# Connectors.net
KiCad netlist of a schematic drawn in Altium Designer
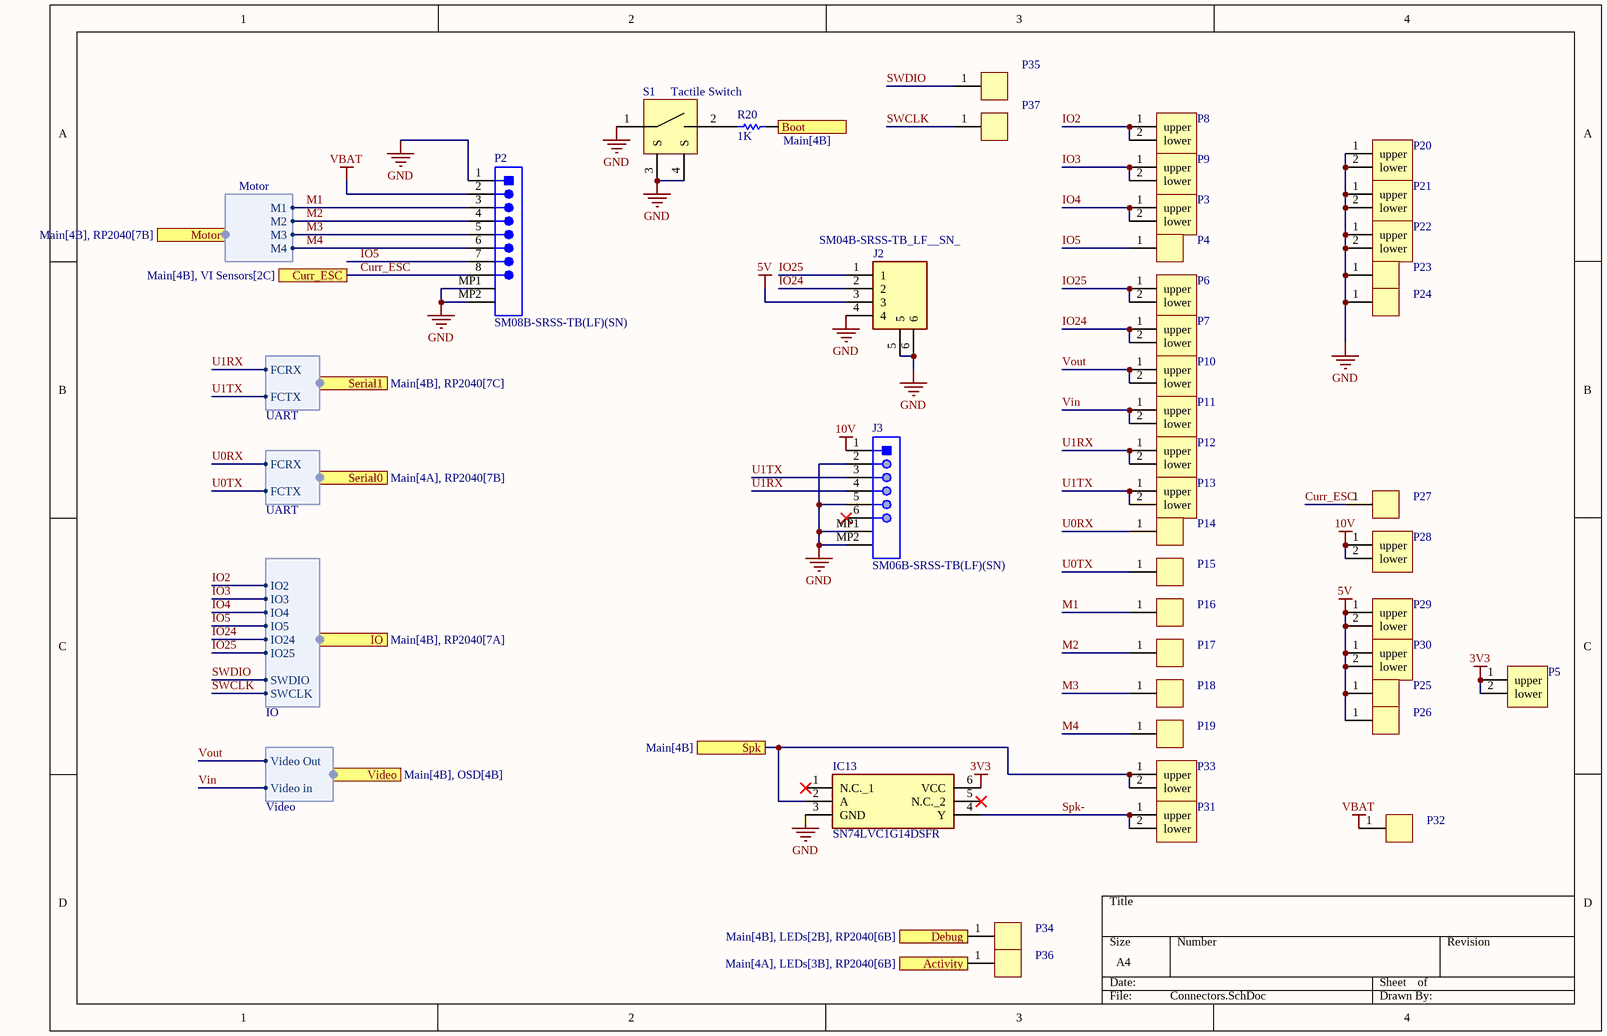
[diagram p0: Connectors.SchDoc]

(export (version "E")
  (design (tool "Eeschema 10.0.6"))
  (components
    (comp (ref "IC13")
      (value "SN74LVC1G14DSFR")
      (footprint "Custom Components:SON35P100X100X40-6N")
      (description "Integrated Circuit")
      (fields (field (name "MOUSER PART NUMBER") "595-SN74LVC1G14DSFR"))
      (libsource (lib "*") (part "SN74LVC1G14DSFR"))
    )
    (comp (ref "J2")
      (value "SM04B-SRSS-TB_LF__SN_")
      (footprint "SM04B-SRSS-TB(LFSN)")
      (description "Connector")
      (fields (field (name "MANUFACTURER_PART_NUMBER") "SM04B-SRSS-TB(LF)(SN)"))
      (libsource (lib "Custom Components") (part "SM04B-SRSS-TB_LF__SN_"))
    )
    (comp (ref "J3")
      (value "SM06B-SRSS-TB(LF)(SN)")
      (footprint "JST-SM06B-SRSS-TB_V")
      (description "Male Header, Pitch 1 mm, 1 x 6 Position, Height 2.95 mm, -25 to 85 degC, RoHS, Tape and Reel")
      (fields (field (name "MANUFACTURER") "JST"))
      (libsource (lib "Altium Content Vault") (part "CN-1P-2M-R6"))
    )
    (comp (ref "P2")
      (value "SM08B-SRSS-TB(LF)(SN)")
      (footprint "JST-SM08B-SRSS-TB_V")
      (description "Male Header, Pitch 1 mm, 1 x 8 Position, Height 2.95 mm, -25 to 85 degC, RoHS, Tape and Reel")
      (fields (field (name "MANUFACTURER") "JST"))
      (libsource (lib "Altium Content Vault") (part "CN-1P-2M-R8"))
    )
    (comp (ref "P3")
      (value "solder pad rounded double sided")
      (footprint "solder pad double sided rounded - duplicate")
      (libsource (lib "Custom Components") (part "solder pad rounded double sided"))
    )
    (comp (ref "P4")
      (value "solder pad rounded single sided")
      (footprint "solder pad single sided rounded")
      (libsource (lib "Custom Components") (part "solder pad rounded single sided"))
    )
    (comp (ref "P5")
      (value "solder pad chamfered double sided")
      (footprint "solder pad double sided chamfered")
      (libsource (lib "Custom Components") (part "solder pad chamfered double sided"))
    )
    (comp (ref "P6")
      (value "solder pad rounded double sided")
      (footprint "solder pad double sided rounded - duplicate")
      (libsource (lib "Custom Components") (part "solder pad rounded double sided"))
    )
    (comp (ref "P7")
      (value "solder pad rounded double sided")
      (footprint "solder pad double sided rounded - duplicate")
      (libsource (lib "Custom Components") (part "solder pad rounded double sided"))
    )
    (comp (ref "P8")
      (value "solder pad rounded double sided")
      (footprint "solder pad double sided rounded - duplicate")
      (libsource (lib "Custom Components") (part "solder pad rounded double sided"))
    )
    (comp (ref "P9")
      (value "solder pad rounded double sided")
      (footprint "solder pad double sided rounded - duplicate")
      (libsource (lib "Custom Components") (part "solder pad rounded double sided"))
    )
    (comp (ref "P10")
      (value "solder pad rounded double sided")
      (footprint "solder pad double sided rounded - duplicate")
      (libsource (lib "Custom Components") (part "solder pad rounded double sided"))
    )
    (comp (ref "P11")
      (value "solder pad rounded double sided")
      (footprint "solder pad double sided rounded - duplicate")
      (libsource (lib "Custom Components") (part "solder pad rounded double sided"))
    )
    (comp (ref "P12")
      (value "solder pad rounded double sided")
      (footprint "solder pad double sided rounded - duplicate")
      (libsource (lib "Custom Components") (part "solder pad rounded double sided"))
    )
    (comp (ref "P13")
      (value "solder pad rounded double sided")
      (footprint "solder pad double sided rounded - duplicate")
      (libsource (lib "Custom Components") (part "solder pad rounded double sided"))
    )
    (comp (ref "P14")
      (value "solder pad rounded single sided")
      (footprint "solder pad single sided rounded")
      (libsource (lib "Custom Components") (part "solder pad rounded single sided"))
    )
    (comp (ref "P15")
      (value "solder pad rounded single sided")
      (footprint "solder pad single sided rounded")
      (libsource (lib "Custom Components") (part "solder pad rounded single sided"))
    )
    (comp (ref "P16")
      (value "solder pad rounded single sided")
      (footprint "solder pad single sided rounded")
      (libsource (lib "Custom Components") (part "solder pad rounded single sided"))
    )
    (comp (ref "P17")
      (value "solder pad rounded single sided")
      (footprint "solder pad single sided rounded")
      (libsource (lib "Custom Components") (part "solder pad rounded single sided"))
    )
    (comp (ref "P18")
      (value "solder pad rounded single sided")
      (footprint "solder pad single sided rounded")
      (libsource (lib "Custom Components") (part "solder pad rounded single sided"))
    )
    (comp (ref "P19")
      (value "solder pad rounded single sided")
      (footprint "solder pad single sided rounded")
      (libsource (lib "Custom Components") (part "solder pad rounded single sided"))
    )
    (comp (ref "P20")
      (value "solder pad square double sided")
      (footprint "solder pad double sided square")
      (libsource (lib "Custom Components") (part "solder pad square double sided"))
    )
    (comp (ref "P21")
      (value "solder pad square double sided")
      (footprint "solder pad double sided square")
      (libsource (lib "Custom Components") (part "solder pad square double sided"))
    )
    (comp (ref "P22")
      (value "solder pad square double sided")
      (footprint "solder pad double sided square")
      (libsource (lib "Custom Components") (part "solder pad square double sided"))
    )
    (comp (ref "P23")
      (value "solder pad square single sided")
      (footprint "solder pad single sided square")
      (libsource (lib "Custom Components") (part "solder pad square single sided"))
    )
    (comp (ref "P24")
      (value "solder pad square single sided")
      (footprint "solder pad single sided square")
      (libsource (lib "Custom Components") (part "solder pad square single sided"))
    )
    (comp (ref "P25")
      (value "solder pad chamfered single sided")
      (footprint "solder pad single sided chamfered")
      (libsource (lib "Custom Components") (part "solder pad chamfered single sided"))
    )
    (comp (ref "P26")
      (value "solder pad chamfered single sided")
      (footprint "solder pad single sided chamfered")
      (libsource (lib "Custom Components") (part "solder pad chamfered single sided"))
    )
    (comp (ref "P27")
      (value "solder pad rounded single sided")
      (footprint "solder pad single sided rounded")
      (libsource (lib "Custom Components") (part "solder pad rounded single sided"))
    )
    (comp (ref "P28")
      (value "solder pad chamfered double sided")
      (footprint "solder pad double sided chamfered")
      (libsource (lib "Custom Components") (part "solder pad chamfered double sided"))
    )
    (comp (ref "P29")
      (value "solder pad chamfered double sided")
      (footprint "solder pad double sided chamfered")
      (libsource (lib "Custom Components") (part "solder pad chamfered double sided"))
    )
    (comp (ref "P30")
      (value "solder pad chamfered double sided")
      (footprint "solder pad double sided chamfered")
      (libsource (lib "Custom Components") (part "solder pad chamfered double sided"))
    )
    (comp (ref "P31")
      (value "solder pad rounded double sided")
      (footprint "solder pad double sided rounded - duplicate")
      (libsource (lib "Custom Components") (part "solder pad rounded double sided"))
    )
    (comp (ref "P32")
      (value "solder pad chamfered single sided")
      (footprint "solder pad single sided chamfered")
      (libsource (lib "Custom Components") (part "solder pad chamfered single sided"))
    )
    (comp (ref "P33")
      (value "solder pad rounded double sided")
      (footprint "solder pad double sided rounded - duplicate")
      (libsource (lib "Custom Components") (part "solder pad rounded double sided"))
    )
    (comp (ref "P34")
      (value "solder pad rounded single sided")
      (footprint "solder pad single sided rounded")
      (libsource (lib "Custom Components") (part "solder pad rounded single sided"))
    )
    (comp (ref "P35")
      (value "solder pad rounded single sided")
      (footprint "solder pad single sided rounded")
      (libsource (lib "Custom Components") (part "solder pad rounded single sided"))
    )
    (comp (ref "P36")
      (value "solder pad rounded single sided")
      (footprint "solder pad single sided rounded")
      (libsource (lib "Custom Components") (part "solder pad rounded single sided"))
    )
    (comp (ref "P37")
      (value "solder pad rounded single sided")
      (footprint "solder pad single sided rounded")
      (libsource (lib "Custom Components") (part "solder pad rounded single sided"))
    )
    (comp (ref "R20")
      (value "1K")
      (footprint "RESC0603(1608)_N")
      (description "Chipwiderstand, SMD, Baureihe MC, 1%")
      (fields (field (name "MANUFACTURER") "Multicomp"))
      (libsource (lib "Standardbauteile") (part "Res 1K"))
    )
    (comp (ref "S1")
      (value "Tactile Switch")
      (footprint "Tactile Switch")
      (libsource (lib "Custom Components") (part "Tactile Switch"))
    )
  )
  (nets
    (net (code "5") (name "/Activity") (class "Default")
      (node (ref "P36") (pin "1") (pinfunction "upper_1") (pintype "passive"))
    )
    (net (code "6") (name "/Boot") (class "Default")
      (node (ref "R20") (pin "2") (pinfunction "2_2") (pintype "passive"))
    )
    (net (code "7") (name "/Curr_ESC") (class "Default")
      (node (ref "P2") (pin "8") (pinfunction "8_8") (pintype "passive"))
      (node (ref "P27") (pin "1") (pinfunction "upper_1") (pintype "passive"))
    )
    (net (code "8") (name "/Debug") (class "Default")
      (node (ref "P34") (pin "1") (pinfunction "upper_1") (pintype "passive"))
    )
    (net (code "9") (name "/IO2") (class "Default")
      (node (ref "P8") (pin "1") (pinfunction "upper_1") (pintype "passive"))
      (node (ref "P8") (pin "2") (pinfunction "lower_2") (pintype "passive"))
    )
    (net (code "10") (name "/IO3") (class "Default")
      (node (ref "P9") (pin "1") (pinfunction "upper_1") (pintype "passive"))
      (node (ref "P9") (pin "2") (pinfunction "lower_2") (pintype "passive"))
    )
    (net (code "11") (name "/IO4") (class "Default")
      (node (ref "P3") (pin "1") (pinfunction "upper_1") (pintype "passive"))
      (node (ref "P3") (pin "2") (pinfunction "lower_2") (pintype "passive"))
    )
    (net (code "12") (name "/IO5") (class "Default")
      (node (ref "P2") (pin "7") (pinfunction "7_7") (pintype "passive"))
      (node (ref "P4") (pin "1") (pinfunction "upper_1") (pintype "passive"))
    )
    (net (code "13") (name "/IO24") (class "Default")
      (node (ref "J2") (pin "2") (pinfunction "2_2") (pintype "passive"))
      (node (ref "P7") (pin "1") (pinfunction "upper_1") (pintype "passive"))
      (node (ref "P7") (pin "2") (pinfunction "lower_2") (pintype "passive"))
    )
    (net (code "14") (name "/IO25") (class "Default")
      (node (ref "J2") (pin "1") (pinfunction "1_1") (pintype "passive"))
      (node (ref "P6") (pin "1") (pinfunction "upper_1") (pintype "passive"))
      (node (ref "P6") (pin "2") (pinfunction "lower_2") (pintype "passive"))
    )
    (net (code "15") (name "/M1") (class "Default")
      (node (ref "P16") (pin "1") (pinfunction "upper_1") (pintype "passive"))
      (node (ref "P2") (pin "3") (pinfunction "3_3") (pintype "passive"))
    )
    (net (code "16") (name "/M2") (class "Default")
      (node (ref "P17") (pin "1") (pinfunction "upper_1") (pintype "passive"))
      (node (ref "P2") (pin "4") (pinfunction "4_4") (pintype "passive"))
    )
    (net (code "17") (name "/M3") (class "Default")
      (node (ref "P18") (pin "1") (pinfunction "upper_1") (pintype "passive"))
      (node (ref "P2") (pin "5") (pinfunction "5_5") (pintype "passive"))
    )
    (net (code "18") (name "/M4") (class "Default")
      (node (ref "P19") (pin "1") (pinfunction "upper_1") (pintype "passive"))
      (node (ref "P2") (pin "6") (pinfunction "6_6") (pintype "passive"))
    )
    (net (code "19") (name "/SWCLK") (class "Default")
      (node (ref "P37") (pin "1") (pinfunction "upper_1") (pintype "passive"))
    )
    (net (code "20") (name "/SWDIO") (class "Default")
      (node (ref "P35") (pin "1") (pinfunction "upper_1") (pintype "passive"))
    )
    (net (code "21") (name "/Spk") (class "Default")
      (node (ref "IC13") (pin "2") (pinfunction "A_2") (pintype "passive"))
      (node (ref "P33") (pin "1") (pinfunction "upper_1") (pintype "passive"))
      (node (ref "P33") (pin "2") (pinfunction "lower_2") (pintype "passive"))
    )
    (net (code "22") (name "/Spk-") (class "Default")
      (node (ref "IC13") (pin "4") (pinfunction "Y_4") (pintype "passive"))
      (node (ref "P31") (pin "1") (pinfunction "upper_1") (pintype "passive"))
      (node (ref "P31") (pin "2") (pinfunction "lower_2") (pintype "passive"))
    )
    (net (code "23") (name "/U0RX") (class "Default")
      (node (ref "P14") (pin "1") (pinfunction "upper_1") (pintype "passive"))
    )
    (net (code "24") (name "/U0TX") (class "Default")
      (node (ref "P15") (pin "1") (pinfunction "upper_1") (pintype "passive"))
    )
    (net (code "25") (name "/U1RX") (class "Default")
      (node (ref "J3") (pin "4") (pinfunction "4_4") (pintype "passive"))
      (node (ref "P12") (pin "1") (pinfunction "upper_1") (pintype "passive"))
      (node (ref "P12") (pin "2") (pinfunction "lower_2") (pintype "passive"))
    )
    (net (code "26") (name "/U1TX") (class "Default")
      (node (ref "J3") (pin "3") (pinfunction "3_3") (pintype "passive"))
      (node (ref "P13") (pin "1") (pinfunction "upper_1") (pintype "passive"))
      (node (ref "P13") (pin "2") (pinfunction "lower_2") (pintype "passive"))
    )
    (net (code "27") (name "/Vin") (class "Default")
      (node (ref "P11") (pin "1") (pinfunction "upper_1") (pintype "passive"))
      (node (ref "P11") (pin "2") (pinfunction "lower_2") (pintype "passive"))
    )
    (net (code "28") (name "/Vout") (class "Default")
      (node (ref "P10") (pin "1") (pinfunction "upper_1") (pintype "passive"))
      (node (ref "P10") (pin "2") (pinfunction "lower_2") (pintype "passive"))
    )
    (net (code "33") (name "3V3") (class "Default")
      (node (ref "IC13") (pin "6") (pinfunction "VCC_6") (pintype "passive"))
      (node (ref "P5") (pin "1") (pinfunction "upper_1") (pintype "passive"))
      (node (ref "P5") (pin "2") (pinfunction "lower_2") (pintype "passive"))
    )
    (net (code "34") (name "5V") (class "Default")
      (node (ref "J2") (pin "3") (pinfunction "3_3") (pintype "passive"))
      (node (ref "P25") (pin "1") (pinfunction "upper_1") (pintype "passive"))
      (node (ref "P26") (pin "1") (pinfunction "upper_1") (pintype "passive"))
      (node (ref "P29") (pin "1") (pinfunction "upper_1") (pintype "passive"))
      (node (ref "P29") (pin "2") (pinfunction "lower_2") (pintype "passive"))
      (node (ref "P30") (pin "1") (pinfunction "upper_1") (pintype "passive"))
      (node (ref "P30") (pin "2") (pinfunction "lower_2") (pintype "passive"))
    )
    (net (code "35") (name "10V") (class "Default")
      (node (ref "J3") (pin "1") (pinfunction "1_1") (pintype "passive"))
      (node (ref "P28") (pin "1") (pinfunction "upper_1") (pintype "passive"))
      (node (ref "P28") (pin "2") (pinfunction "lower_2") (pintype "passive"))
    )
    (net (code "36") (name "GND") (class "Default")
      (node (ref "IC13") (pin "3") (pinfunction "GND_3") (pintype "passive"))
      (node (ref "J2") (pin "4") (pinfunction "4_4") (pintype "passive"))
      (node (ref "J2") (pin "5") (pinfunction "5_5") (pintype "passive"))
      (node (ref "J2") (pin "6") (pinfunction "6_6") (pintype "passive"))
      (node (ref "J3") (pin "2") (pinfunction "2_2") (pintype "passive"))
      (node (ref "J3") (pin "5") (pinfunction "5_5") (pintype "passive"))
      (node (ref "J3") (pin "MP1") (pinfunction "MP1_MP1") (pintype "passive"))
      (node (ref "J3") (pin "MP2") (pinfunction "MP2_MP2") (pintype "passive"))
      (node (ref "P2") (pin "1") (pinfunction "1_1") (pintype "passive"))
      (node (ref "P2") (pin "MP1") (pinfunction "MP1_MP1") (pintype "passive"))
      (node (ref "P2") (pin "MP2") (pinfunction "MP2_MP2") (pintype "passive"))
      (node (ref "P20") (pin "1") (pinfunction "upper_1") (pintype "passive"))
      (node (ref "P20") (pin "2") (pinfunction "lower_2") (pintype "passive"))
      (node (ref "P21") (pin "1") (pinfunction "upper_1") (pintype "passive"))
      (node (ref "P21") (pin "2") (pinfunction "lower_2") (pintype "passive"))
      (node (ref "P22") (pin "1") (pinfunction "upper_1") (pintype "passive"))
      (node (ref "P22") (pin "2") (pinfunction "lower_2") (pintype "passive"))
      (node (ref "P23") (pin "1") (pinfunction "upper_1") (pintype "passive"))
      (node (ref "P24") (pin "1") (pinfunction "upper_1") (pintype "passive"))
      (node (ref "S1") (pin "1") (pintype "passive"))
      (node (ref "S1") (pin "3") (pinfunction "S_3") (pintype "passive"))
      (node (ref "S1") (pin "4") (pinfunction "S_4") (pintype "passive"))
    )
    (net (code "37") (name "Net-(R20-Pad1)") (class "Default")
      (node (ref "R20") (pin "1") (pinfunction "1_1") (pintype "passive"))
      (node (ref "S1") (pin "2") (pintype "passive"))
    )
    (net (code "38") (name "VBAT") (class "Default")
      (node (ref "P2") (pin "2") (pinfunction "2_2") (pintype "passive"))
      (node (ref "P32") (pin "1") (pinfunction "upper_1") (pintype "passive"))
    )
    (net (code "39") (name "unconnected-(IC13-N.C._1-Pad1)") (class "Default")
      (node (ref "IC13") (pin "1") (pinfunction "N.C._1_1") (pintype "passive+no_connect"))
    )
    (net (code "40") (name "unconnected-(IC13-N.C._2-Pad5)") (class "Default")
      (node (ref "IC13") (pin "5") (pinfunction "N.C._2_5") (pintype "passive+no_connect"))
    )
    (net (code "41") (name "unconnected-(J3-Pad6)") (class "Default")
      (node (ref "J3") (pin "6") (pinfunction "6_6") (pintype "passive+no_connect"))
    )
  )
)
